# raspirepcol.net
KiCad netlist of a schematic drawn in EAGLE
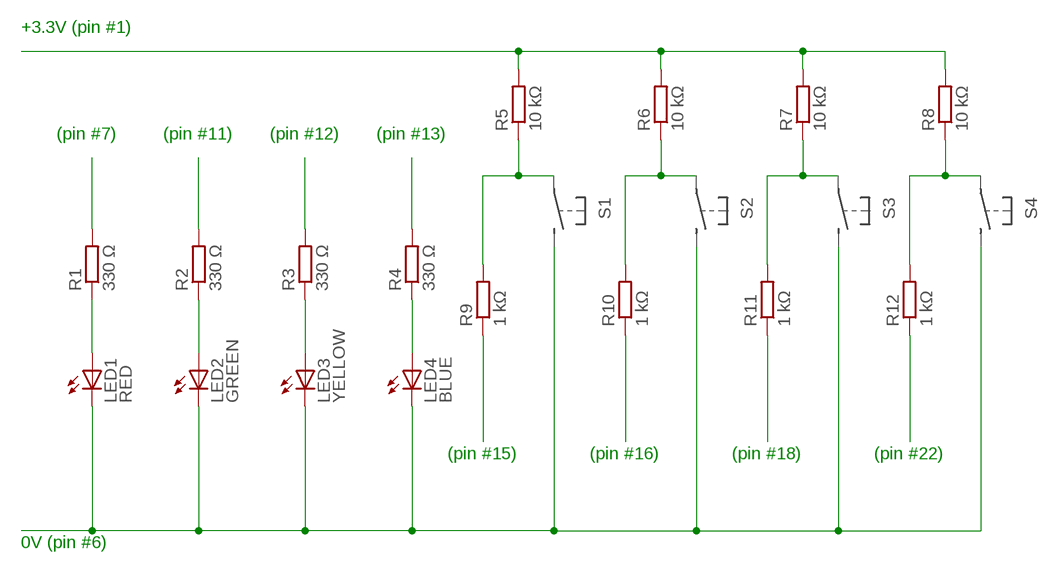
[diagram p0: schematic, sheet 1]

(export (version "E")
  (design (tool "Eeschema 10.0.6"))
  (components
    (comp (ref "LED1")
      (value "RED")
      (footprint "eagle-import:P47F-BOTTOM")
      (libsource (lib "eagle-import") (part "P4-BOTTOMLA"))
    )
    (comp (ref "LED2")
      (value "GREEN")
      (footprint "eagle-import:P47F-BOTTOM")
      (libsource (lib "eagle-import") (part "P4-BOTTOMLA"))
    )
    (comp (ref "LED3")
      (value "YELLOW")
      (footprint "eagle-import:P47F-BOTTOM")
      (libsource (lib "eagle-import") (part "P4-BOTTOMLA"))
    )
    (comp (ref "LED4")
      (value "BLUE")
      (footprint "eagle-import:P47F-BOTTOM")
      (libsource (lib "eagle-import") (part "P4-BOTTOMLA"))
    )
    (comp (ref "R1")
      (value "330 Ω")
      (footprint "eagle-import:0204V")
      (libsource (lib "eagle-import") (part "R-EU_0204/2V"))
    )
    (comp (ref "R2")
      (value "330 Ω")
      (footprint "eagle-import:0204V")
      (libsource (lib "eagle-import") (part "R-EU_0204/2V"))
    )
    (comp (ref "R3")
      (value "330 Ω")
      (footprint "eagle-import:0204V")
      (libsource (lib "eagle-import") (part "R-EU_0204/2V"))
    )
    (comp (ref "R4")
      (value "330 Ω")
      (footprint "eagle-import:0204V")
      (libsource (lib "eagle-import") (part "R-EU_0204/2V"))
    )
    (comp (ref "R5")
      (value "10 kΩ")
      (footprint "eagle-import:0204V")
      (libsource (lib "eagle-import") (part "R-EU_0204/2V"))
    )
    (comp (ref "R6")
      (value "10 kΩ")
      (footprint "eagle-import:0204V")
      (libsource (lib "eagle-import") (part "R-EU_0204/2V"))
    )
    (comp (ref "R7")
      (value "10 kΩ")
      (footprint "eagle-import:0204V")
      (libsource (lib "eagle-import") (part "R-EU_0204/2V"))
    )
    (comp (ref "R8")
      (value "10 kΩ")
      (footprint "eagle-import:0204V")
      (libsource (lib "eagle-import") (part "R-EU_0204/2V"))
    )
    (comp (ref "R9")
      (value "1 kΩ")
      (footprint "eagle-import:0204V")
      (libsource (lib "eagle-import") (part "R-EU_0204/2V"))
    )
    (comp (ref "R10")
      (value "1 kΩ")
      (footprint "eagle-import:0204V")
      (libsource (lib "eagle-import") (part "R-EU_0204/2V"))
    )
    (comp (ref "R11")
      (value "1 kΩ")
      (footprint "eagle-import:0204V")
      (libsource (lib "eagle-import") (part "R-EU_0204/2V"))
    )
    (comp (ref "R12")
      (value "1 kΩ")
      (footprint "eagle-import:0204V")
      (libsource (lib "eagle-import") (part "R-EU_0204/2V"))
    )
  )
  (nets
    (net (code "1") (name "Net-(LED1-PadA)") (class "Default")
      (node (ref "LED1") (pin "A") (pinfunction "A_A") (pintype "passive"))
      (node (ref "R1") (pin "1") (pinfunction "1_1") (pintype "passive"))
    )
    (net (code "2") (name "Net-(LED1-PadC)") (class "Default")
      (node (ref "LED1") (pin "C") (pinfunction "C_C") (pintype "passive"))
      (node (ref "LED2") (pin "C") (pinfunction "C_C") (pintype "passive"))
      (node (ref "LED3") (pin "C") (pinfunction "C_C") (pintype "passive"))
      (node (ref "LED4") (pin "C") (pinfunction "C_C") (pintype "passive"))
    )
    (net (code "3") (name "Net-(LED2-PadA)") (class "Default")
      (node (ref "LED2") (pin "A") (pinfunction "A_A") (pintype "passive"))
      (node (ref "R2") (pin "1") (pinfunction "1_1") (pintype "passive"))
    )
    (net (code "4") (name "Net-(LED3-PadA)") (class "Default")
      (node (ref "LED3") (pin "A") (pinfunction "A_A") (pintype "passive"))
      (node (ref "R3") (pin "1") (pinfunction "1_1") (pintype "passive"))
    )
    (net (code "5") (name "Net-(LED4-PadA)") (class "Default")
      (node (ref "LED4") (pin "A") (pinfunction "A_A") (pintype "passive"))
      (node (ref "R4") (pin "1") (pinfunction "1_1") (pintype "passive"))
    )
    (net (code "6") (name "Net-(R5-Pad1)") (class "Default")
      (node (ref "R5") (pin "1") (pinfunction "1_1") (pintype "passive"))
      (node (ref "R9") (pin "2") (pinfunction "2_2") (pintype "passive"))
    )
    (net (code "7") (name "Net-(R5-Pad2)") (class "Default")
      (node (ref "R5") (pin "2") (pinfunction "2_2") (pintype "passive"))
      (node (ref "R6") (pin "2") (pinfunction "2_2") (pintype "passive"))
      (node (ref "R7") (pin "2") (pinfunction "2_2") (pintype "passive"))
      (node (ref "R8") (pin "2") (pinfunction "2_2") (pintype "passive"))
    )
    (net (code "8") (name "Net-(R10-Pad2)") (class "Default")
      (node (ref "R10") (pin "2") (pinfunction "2_2") (pintype "passive"))
      (node (ref "R6") (pin "1") (pinfunction "1_1") (pintype "passive"))
    )
    (net (code "9") (name "Net-(R11-Pad2)") (class "Default")
      (node (ref "R11") (pin "2") (pinfunction "2_2") (pintype "passive"))
      (node (ref "R7") (pin "1") (pinfunction "1_1") (pintype "passive"))
    )
    (net (code "10") (name "Net-(R12-Pad2)") (class "Default")
      (node (ref "R12") (pin "2") (pinfunction "2_2") (pintype "passive"))
      (node (ref "R8") (pin "1") (pinfunction "1_1") (pintype "passive"))
    )
    (net (code "11") (name "unconnected-(R1-Pad2)") (class "Default")
      (node (ref "R1") (pin "2") (pinfunction "2_2") (pintype "passive"))
    )
    (net (code "12") (name "unconnected-(R2-Pad2)") (class "Default")
      (node (ref "R2") (pin "2") (pinfunction "2_2") (pintype "passive"))
    )
    (net (code "13") (name "unconnected-(R3-Pad2)") (class "Default")
      (node (ref "R3") (pin "2") (pinfunction "2_2") (pintype "passive"))
    )
    (net (code "14") (name "unconnected-(R4-Pad2)") (class "Default")
      (node (ref "R4") (pin "2") (pinfunction "2_2") (pintype "passive"))
    )
    (net (code "15") (name "unconnected-(R9-Pad1)") (class "Default")
      (node (ref "R9") (pin "1") (pinfunction "1_1") (pintype "passive"))
    )
    (net (code "16") (name "unconnected-(R10-Pad1)") (class "Default")
      (node (ref "R10") (pin "1") (pinfunction "1_1") (pintype "passive"))
    )
    (net (code "17") (name "unconnected-(R11-Pad1)") (class "Default")
      (node (ref "R11") (pin "1") (pinfunction "1_1") (pintype "passive"))
    )
    (net (code "18") (name "unconnected-(R12-Pad1)") (class "Default")
      (node (ref "R12") (pin "1") (pinfunction "1_1") (pintype "passive"))
    )
  )
)
